# IDEAdapterSingle.net
KiCad netlist of a schematic drawn in EAGLE
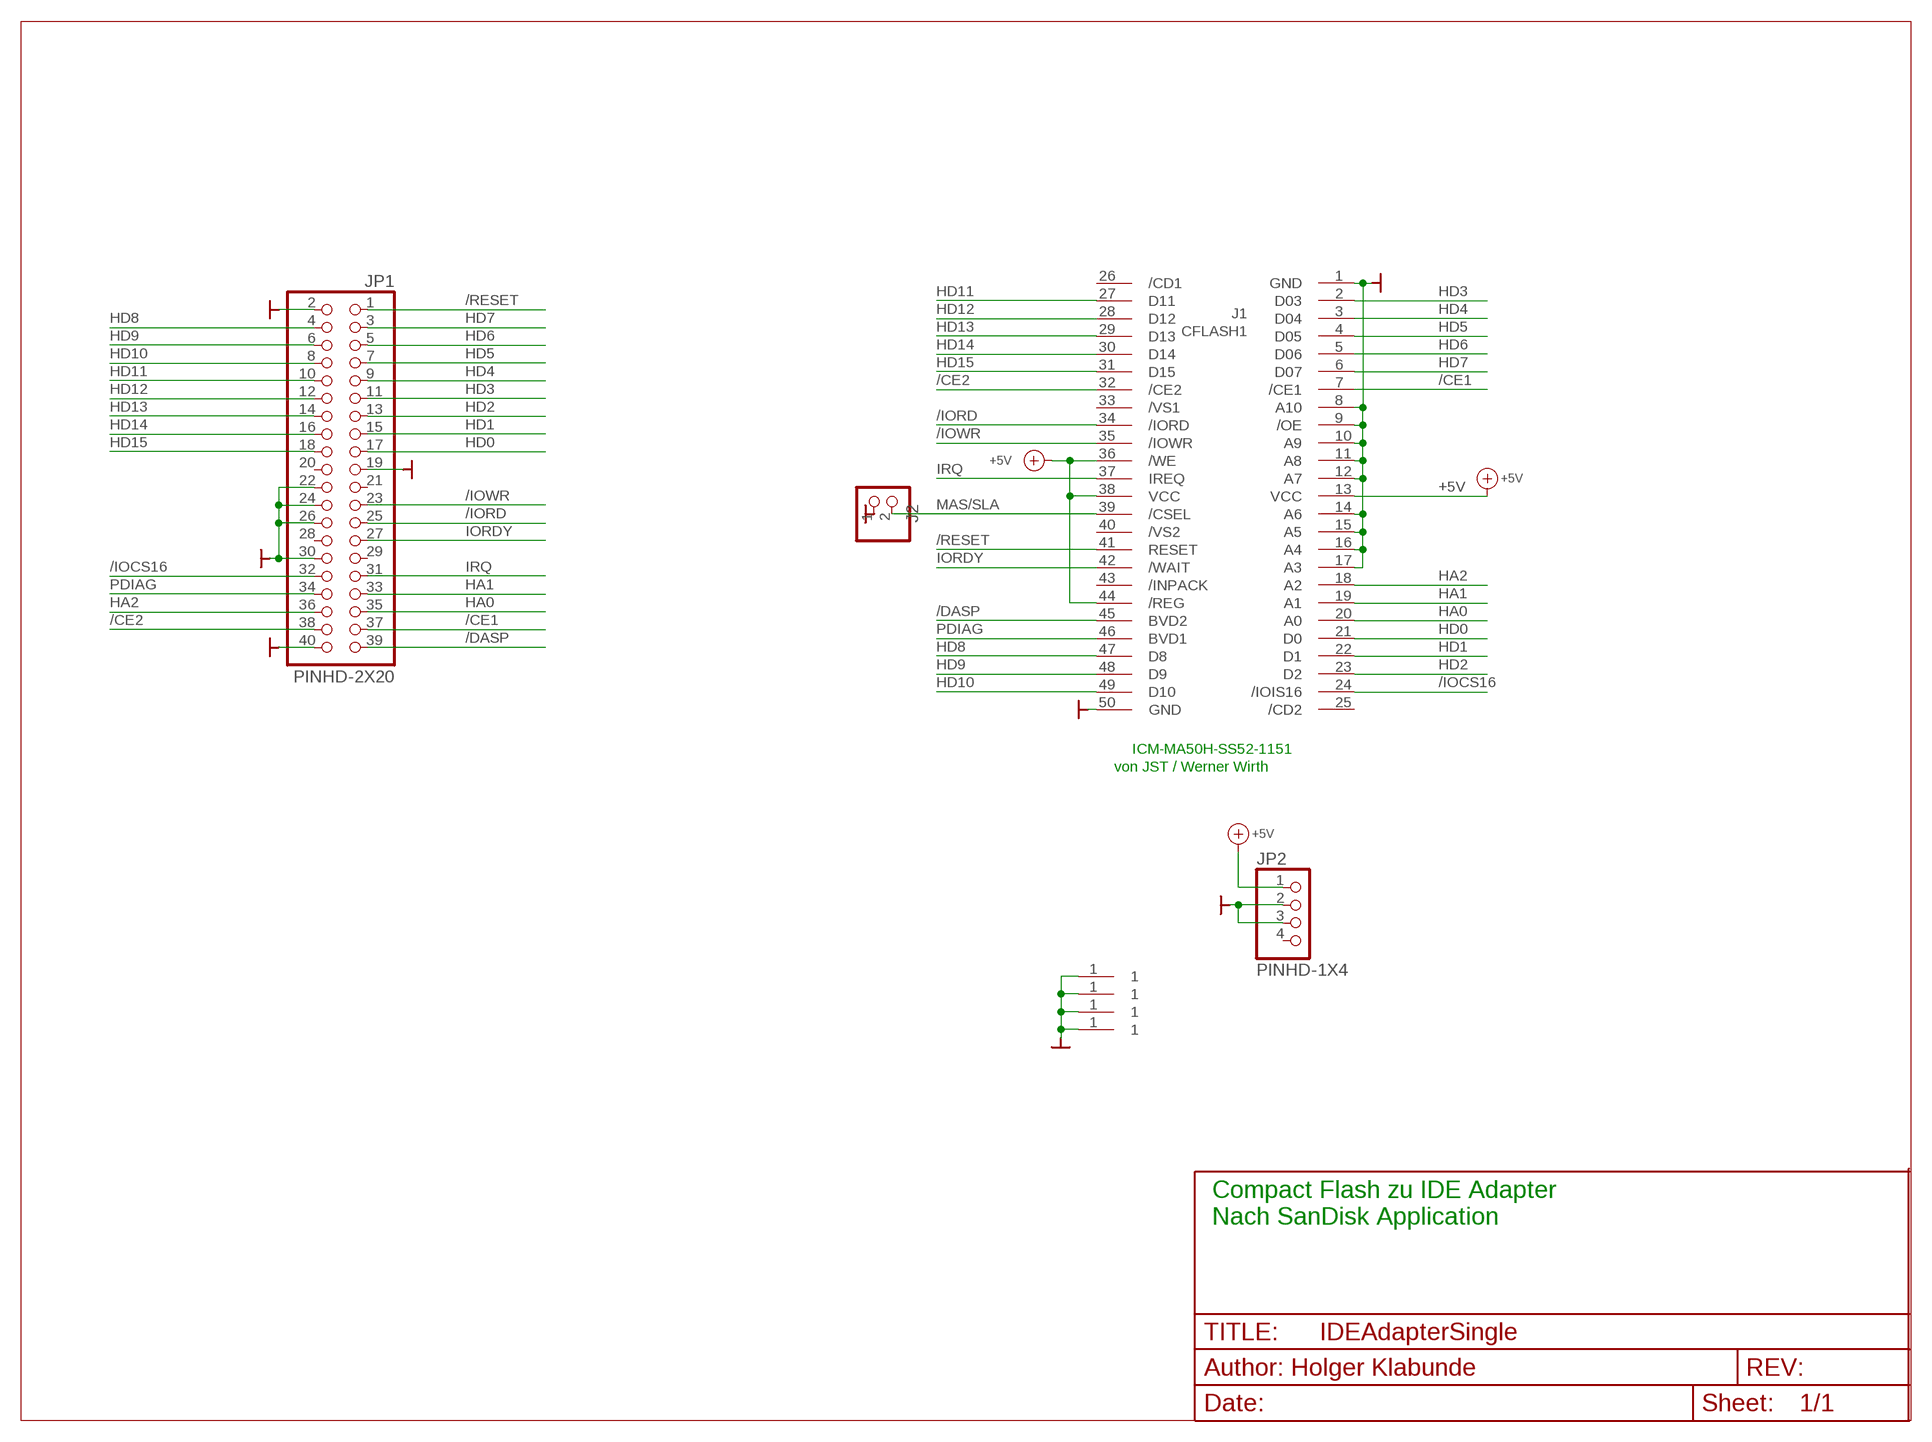
[diagram p0: schematic, sheet 1]

(export (version "E")
  (design (tool "Eeschema 10.0.6"))
  (components
    (comp (ref "J1")
      (value "CFLASH1")
      (footprint "eagle-import:CFSMT")
      (libsource (lib "eagle-import") (part "CFLASH1"))
    )
    (comp (ref "J2")
      (value "JUMPER")
      (footprint "eagle-import:1X02")
      (libsource (lib "eagle-import") (part "PINHD-1X2"))
    )
    (comp (ref "JP1")
      (value "PINHD-2X20")
      (footprint "eagle-import:2X20")
      (libsource (lib "eagle-import") (part "PINHD-2X20"))
    )
    (comp (ref "JP2")
      (value "PINHD-1X4")
      (footprint "eagle-import:1X04")
      (libsource (lib "eagle-import") (part "PINHD-1X4"))
    )
    (comp (ref "U$13")
      (value "BOHRUNG")
      (footprint "eagle-import:BOHRUNG")
      (libsource (lib "eagle-import") (part "BOHRUNG"))
    )
    (comp (ref "U$14")
      (value "BOHRUNG")
      (footprint "eagle-import:BOHRUNG")
      (libsource (lib "eagle-import") (part "BOHRUNG"))
    )
    (comp (ref "U$16")
      (value "BOHRUNG")
      (footprint "eagle-import:BOHRUNG")
      (libsource (lib "eagle-import") (part "BOHRUNG"))
    )
    (comp (ref "U$17")
      (value "BOHRUNG")
      (footprint "eagle-import:BOHRUNG")
      (libsource (lib "eagle-import") (part "BOHRUNG"))
    )
  )
  (nets
    (net (code "1") (name "+5V") (class "Default")
      (node (ref "J1") (pin "13") (pinfunction "VCC_13") (pintype "power_in"))
      (node (ref "J1") (pin "36") (pinfunction "/WE_36") (pintype "input"))
      (node (ref "J1") (pin "38") (pinfunction "VCC_38") (pintype "power_in"))
      (node (ref "J1") (pin "44") (pinfunction "/REG_44") (pintype "input"))
      (node (ref "JP2") (pin "1") (pinfunction "1_1") (pintype "passive"))
    )
    (net (code "2") (name "/HA0") (class "Default")
      (node (ref "J1") (pin "20") (pinfunction "A0_20") (pintype "input"))
      (node (ref "JP1") (pin "35") (pinfunction "35_35") (pintype "passive"))
    )
    (net (code "3") (name "/HA1") (class "Default")
      (node (ref "J1") (pin "19") (pinfunction "A1_19") (pintype "input"))
      (node (ref "JP1") (pin "33") (pinfunction "33_33") (pintype "passive"))
    )
    (net (code "4") (name "/HA2") (class "Default")
      (node (ref "J1") (pin "18") (pinfunction "A2_18") (pintype "input"))
      (node (ref "JP1") (pin "36") (pinfunction "36_36") (pintype "passive"))
    )
    (net (code "5") (name "/HD0") (class "Default")
      (node (ref "J1") (pin "21") (pinfunction "D0_21") (pintype "bidirectional"))
      (node (ref "JP1") (pin "17") (pinfunction "17_17") (pintype "passive"))
    )
    (net (code "6") (name "/HD1") (class "Default")
      (node (ref "J1") (pin "22") (pinfunction "D1_22") (pintype "bidirectional"))
      (node (ref "JP1") (pin "15") (pinfunction "15_15") (pintype "passive"))
    )
    (net (code "7") (name "/HD2") (class "Default")
      (node (ref "J1") (pin "23") (pinfunction "D2_23") (pintype "bidirectional"))
      (node (ref "JP1") (pin "13") (pinfunction "13_13") (pintype "passive"))
    )
    (net (code "8") (name "/HD3") (class "Default")
      (node (ref "J1") (pin "2") (pinfunction "D03_2") (pintype "bidirectional"))
      (node (ref "JP1") (pin "11") (pinfunction "11_11") (pintype "passive"))
    )
    (net (code "9") (name "/HD4") (class "Default")
      (node (ref "J1") (pin "3") (pinfunction "D04_3") (pintype "bidirectional"))
      (node (ref "JP1") (pin "9") (pinfunction "9_9") (pintype "passive"))
    )
    (net (code "10") (name "/HD5") (class "Default")
      (node (ref "J1") (pin "4") (pinfunction "D05_4") (pintype "bidirectional"))
      (node (ref "JP1") (pin "7") (pinfunction "7_7") (pintype "passive"))
    )
    (net (code "11") (name "/HD6") (class "Default")
      (node (ref "J1") (pin "5") (pinfunction "D06_5") (pintype "bidirectional"))
      (node (ref "JP1") (pin "5") (pinfunction "5_5") (pintype "passive"))
    )
    (net (code "12") (name "/HD7") (class "Default")
      (node (ref "J1") (pin "6") (pinfunction "D07_6") (pintype "bidirectional"))
      (node (ref "JP1") (pin "3") (pinfunction "3_3") (pintype "passive"))
    )
    (net (code "13") (name "/HD8") (class "Default")
      (node (ref "J1") (pin "47") (pinfunction "D8_47") (pintype "bidirectional"))
      (node (ref "JP1") (pin "4") (pinfunction "4_4") (pintype "passive"))
    )
    (net (code "14") (name "/HD9") (class "Default")
      (node (ref "J1") (pin "48") (pinfunction "D9_48") (pintype "bidirectional"))
      (node (ref "JP1") (pin "6") (pinfunction "6_6") (pintype "passive"))
    )
    (net (code "15") (name "/HD10") (class "Default")
      (node (ref "J1") (pin "49") (pinfunction "D10_49") (pintype "bidirectional"))
      (node (ref "JP1") (pin "8") (pinfunction "8_8") (pintype "passive"))
    )
    (net (code "16") (name "/HD11") (class "Default")
      (node (ref "J1") (pin "27") (pinfunction "D11_27") (pintype "bidirectional"))
      (node (ref "JP1") (pin "10") (pinfunction "10_10") (pintype "passive"))
    )
    (net (code "17") (name "/HD12") (class "Default")
      (node (ref "J1") (pin "28") (pinfunction "D12_28") (pintype "bidirectional"))
      (node (ref "JP1") (pin "12") (pinfunction "12_12") (pintype "passive"))
    )
    (net (code "18") (name "/HD13") (class "Default")
      (node (ref "J1") (pin "29") (pinfunction "D13_29") (pintype "bidirectional"))
      (node (ref "JP1") (pin "14") (pinfunction "14_14") (pintype "passive"))
    )
    (net (code "19") (name "/HD14") (class "Default")
      (node (ref "J1") (pin "30") (pinfunction "D14_30") (pintype "bidirectional"))
      (node (ref "JP1") (pin "16") (pinfunction "16_16") (pintype "passive"))
    )
    (net (code "20") (name "/HD15") (class "Default")
      (node (ref "J1") (pin "31") (pinfunction "D15_31") (pintype "bidirectional"))
      (node (ref "JP1") (pin "18") (pinfunction "18_18") (pintype "passive"))
    )
    (net (code "21") (name "/IORDY") (class "Default")
      (node (ref "J1") (pin "42") (pinfunction "/WAIT_42") (pintype "bidirectional"))
      (node (ref "JP1") (pin "27") (pinfunction "27_27") (pintype "passive"))
    )
    (net (code "22") (name "/IRQ") (class "Default")
      (node (ref "J1") (pin "37") (pinfunction "IREQ_37") (pintype "bidirectional"))
      (node (ref "JP1") (pin "31") (pinfunction "31_31") (pintype "passive"))
    )
    (net (code "23") (name "/MAS{slash}SLA") (class "Default")
      (node (ref "J1") (pin "39") (pinfunction "/CSEL_39") (pintype "input"))
      (node (ref "J2") (pin "2") (pinfunction "2_2") (pintype "passive"))
    )
    (net (code "24") (name "/PDIAG") (class "Default")
      (node (ref "J1") (pin "46") (pinfunction "BVD1_46") (pintype "input"))
      (node (ref "JP1") (pin "34") (pinfunction "34_34") (pintype "passive"))
    )
    (net (code "25") (name "/{slash}CE1") (class "Default")
      (node (ref "J1") (pin "7") (pinfunction "/CE1_7") (pintype "input"))
      (node (ref "JP1") (pin "37") (pinfunction "37_37") (pintype "passive"))
    )
    (net (code "26") (name "/{slash}CE2") (class "Default")
      (node (ref "J1") (pin "32") (pinfunction "/CE2_32") (pintype "input"))
      (node (ref "JP1") (pin "38") (pinfunction "38_38") (pintype "passive"))
    )
    (net (code "27") (name "/{slash}DASP") (class "Default")
      (node (ref "J1") (pin "45") (pinfunction "BVD2_45") (pintype "input"))
      (node (ref "JP1") (pin "39") (pinfunction "39_39") (pintype "passive"))
    )
    (net (code "28") (name "/{slash}IOCS16") (class "Default")
      (node (ref "J1") (pin "24") (pinfunction "/IOIS16_24") (pintype "input"))
      (node (ref "JP1") (pin "32") (pinfunction "32_32") (pintype "passive"))
    )
    (net (code "29") (name "/{slash}IORD") (class "Default")
      (node (ref "J1") (pin "34") (pinfunction "/IORD_34") (pintype "input"))
      (node (ref "JP1") (pin "25") (pinfunction "25_25") (pintype "passive"))
    )
    (net (code "30") (name "/{slash}IOWR") (class "Default")
      (node (ref "J1") (pin "35") (pinfunction "/IOWR_35") (pintype "input"))
      (node (ref "JP1") (pin "23") (pinfunction "23_23") (pintype "passive"))
    )
    (net (code "31") (name "/{slash}RESET") (class "Default")
      (node (ref "J1") (pin "41") (pinfunction "RESET_41") (pintype "input"))
      (node (ref "JP1") (pin "1") (pinfunction "1_1") (pintype "passive"))
    )
    (net (code "32") (name "GND") (class "Default")
      (node (ref "J1") (pin "1") (pinfunction "GND_1") (pintype "power_in"))
      (node (ref "J1") (pin "10") (pinfunction "A9_10") (pintype "input"))
      (node (ref "J1") (pin "11") (pinfunction "A8_11") (pintype "input"))
      (node (ref "J1") (pin "12") (pinfunction "A7_12") (pintype "input"))
      (node (ref "J1") (pin "14") (pinfunction "A6_14") (pintype "input"))
      (node (ref "J1") (pin "15") (pinfunction "A5_15") (pintype "input"))
      (node (ref "J1") (pin "16") (pinfunction "A4_16") (pintype "input"))
      (node (ref "J1") (pin "17") (pinfunction "A3_17") (pintype "input"))
      (node (ref "J1") (pin "50") (pinfunction "GND_50") (pintype "power_in"))
      (node (ref "J1") (pin "8") (pinfunction "A10_8") (pintype "input"))
      (node (ref "J1") (pin "9") (pinfunction "/OE_9") (pintype "input"))
      (node (ref "J2") (pin "1") (pinfunction "1_1") (pintype "passive"))
      (node (ref "JP1") (pin "19") (pinfunction "19_19") (pintype "passive"))
      (node (ref "JP1") (pin "2") (pinfunction "2_2") (pintype "passive"))
      (node (ref "JP1") (pin "22") (pinfunction "22_22") (pintype "passive"))
      (node (ref "JP1") (pin "24") (pinfunction "24_24") (pintype "passive"))
      (node (ref "JP1") (pin "26") (pinfunction "26_26") (pintype "passive"))
      (node (ref "JP1") (pin "30") (pinfunction "30_30") (pintype "passive"))
      (node (ref "JP1") (pin "40") (pinfunction "40_40") (pintype "passive"))
      (node (ref "JP2") (pin "2") (pinfunction "2_2") (pintype "passive"))
      (node (ref "JP2") (pin "3") (pinfunction "3_3") (pintype "passive"))
      (node (ref "U$13") (pin "1") (pinfunction "1_1") (pintype "bidirectional"))
      (node (ref "U$14") (pin "1") (pinfunction "1_1") (pintype "bidirectional"))
      (node (ref "U$16") (pin "1") (pinfunction "1_1") (pintype "bidirectional"))
      (node (ref "U$17") (pin "1") (pinfunction "1_1") (pintype "bidirectional"))
    )
    (net (code "33") (name "unconnected-(J1-{slash}CD1-Pad26)") (class "Default")
      (node (ref "J1") (pin "26") (pinfunction "/CD1_26") (pintype "input"))
    )
    (net (code "34") (name "unconnected-(J1-{slash}CD2-Pad25)") (class "Default")
      (node (ref "J1") (pin "25") (pinfunction "/CD2_25") (pintype "input"))
    )
    (net (code "35") (name "unconnected-(J1-{slash}INPACK-Pad43)") (class "Default")
      (node (ref "J1") (pin "43") (pinfunction "/INPACK_43") (pintype "input"))
    )
    (net (code "36") (name "unconnected-(J1-{slash}VS1-Pad33)") (class "Default")
      (node (ref "J1") (pin "33") (pinfunction "/VS1_33") (pintype "input"))
    )
    (net (code "37") (name "unconnected-(J1-{slash}VS2-Pad40)") (class "Default")
      (node (ref "J1") (pin "40") (pinfunction "/VS2_40") (pintype "input"))
    )
    (net (code "38") (name "unconnected-(JP1-Pad20)") (class "Default")
      (node (ref "JP1") (pin "20") (pinfunction "20_20") (pintype "passive"))
    )
    (net (code "39") (name "unconnected-(JP1-Pad21)") (class "Default")
      (node (ref "JP1") (pin "21") (pinfunction "21_21") (pintype "passive"))
    )
    (net (code "40") (name "unconnected-(JP1-Pad28)") (class "Default")
      (node (ref "JP1") (pin "28") (pinfunction "28_28") (pintype "passive"))
    )
    (net (code "41") (name "unconnected-(JP1-Pad29)") (class "Default")
      (node (ref "JP1") (pin "29") (pinfunction "29_29") (pintype "passive"))
    )
    (net (code "42") (name "unconnected-(JP2-Pad4)") (class "Default")
      (node (ref "JP2") (pin "4") (pinfunction "4_4") (pintype "passive"))
    )
  )
)
